# Linear_Power.net
KiCad netlist of a schematic drawn in Altium Designer
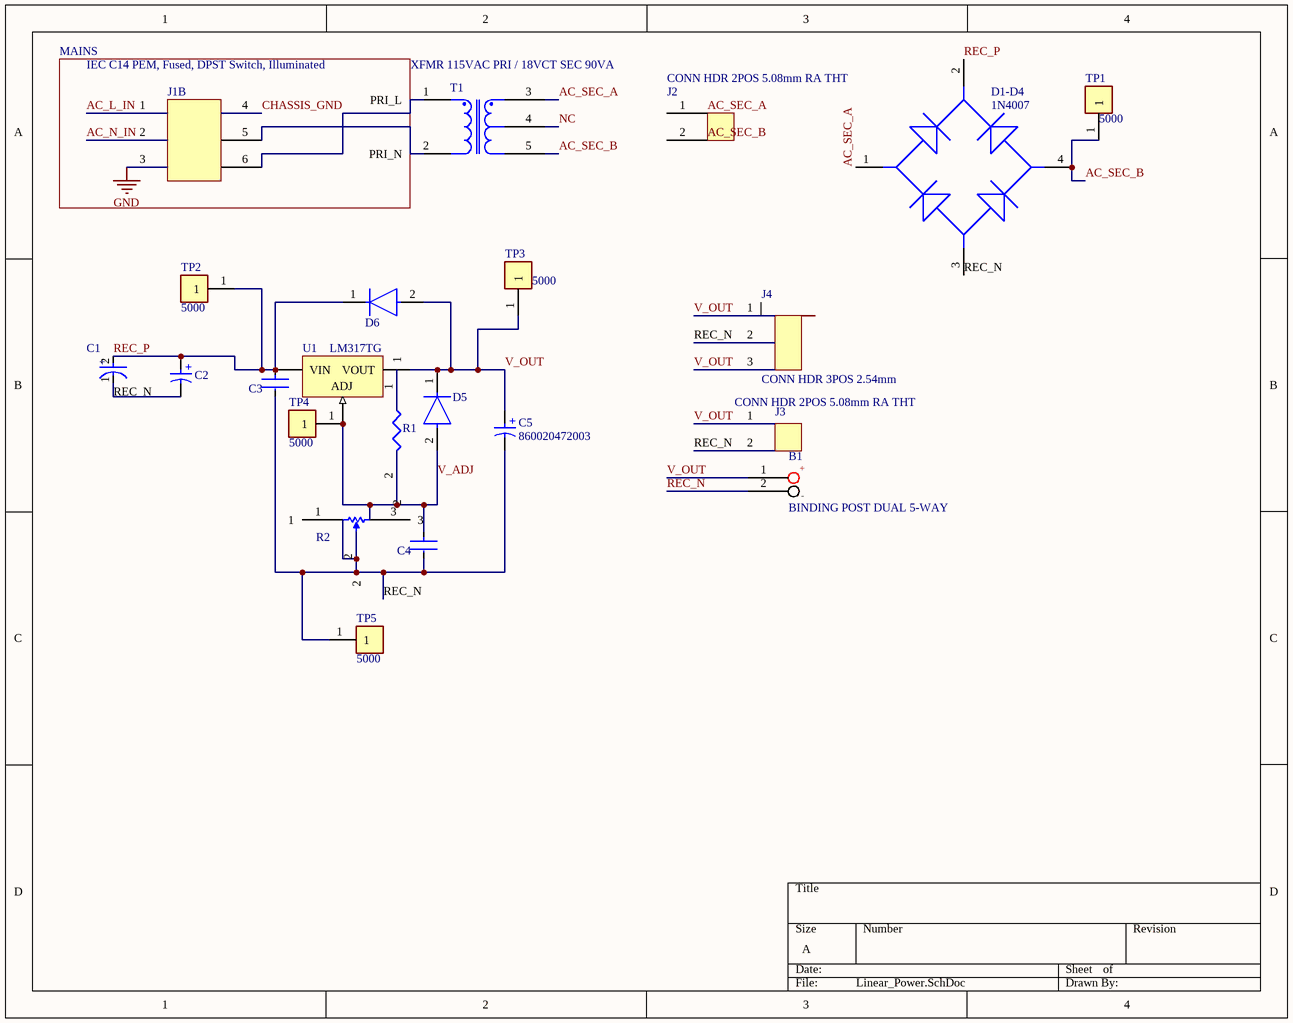
[diagram p0: Linear_Power.SchDoc]

(export (version "E")
  (design (tool "Eeschema 10.0.6"))
  (components
    (comp (ref "B1") (value "BINDING POST DUAL 5-WAY") (libsource (lib "Schlib1") (part "BU-P6883")))
    (comp (ref "C1")
      (value "UPW1V222MHD6")
      (footprint "FP-227AVG035MFBJ-MFG")
      (description "227AVG035MFBJ AVG Series 35 V 220 uF 8 x 12 mm LS=3.5 mm Radial Aluminum Polymer Capacitor")
      (fields (field (name "TOLERANCE") "20%"))
      (libsource (lib "Altium Content Vault") (part "a00bbbee19879c290e62620ae7e47b1"))
    )
    (comp (ref "C2")
      (value "UPJ1V101MPD")
      (footprint "WCAP-ATLI_D5H11")
      (description "WCAP-ATLI Aluminum Electrolytic Capacitors")
      (fields (field (name "TOLERANCE") "20%"))
      (libsource (lib "Altium Content Vault") (part "Capacitor_Polarized"))
    )
    (comp (ref "C3")
      (value "C410C104Z5U5TA7200")
      (footprint "FP-RHE0K1-MFG")
      (description "Multilayer Ceramic Capacitor, 0.1 uF, 50 V, -20%, +80%, Z5U, Axial Leaded")
      (libsource (lib "Altium Content Vault") (part "b4654b650e69147ec39a6b967a45e02"))
    )
    (comp (ref "C4")
      (value "C410C104Z5U5TA7200")
      (footprint "FP-RHE0K1-MFG")
      (description "Multilayer Ceramic Capacitor, 0.1 uF, 50 V, -20%, +80%, Z5U, Axial Leaded")
      (libsource (lib "Altium Content Vault") (part "b4654b650e69147ec39a6b967a45e02"))
    )
    (comp (ref "C5")
      (value "860020472003")
      (footprint "WCAP-ATG5_D5H11")
      (description "860020472003 WCAP-ATG5 Aluminum Electrolytic Capacitors")
      (fields (field (name "TOLERANCE") "20%"))
      (libsource (lib "Altium Content Vault") (part "Capacitor_Polarized"))
    )
    (comp (ref "D1-D4")
      (value "1N4007")
      (footprint "FP-KBJ-MFG")
      (description "BRIDGE RECT 1PHASE 800V 6A KBJ")
      (fields (field (name "MANUFACTURER") "Diodes") (field (name "MANUFACTURER PART NUMBER") "KBJ608G"))
      (libsource (lib "Altium Content Vault") (part "19e15813eaf9f16eb36100cfe986ca5"))
    )
    (comp (ref "D5")
      (value "1N4007")
      (footprint "FP-1N4007-MFG")
      (description "Rectifier diode 1000 V 1 A DO-41, ,")
      (fields
        (field (name "MANUFACTURER") "Diotec")
        (field (name "OCTOPART") "https://octopart.com/1n4007-diotec-4040411")
      )
      (libsource (lib "Altium Content Vault") (part "d7152d700b627762746794eb795d46e"))
    )
    (comp (ref "D6")
      (value "1N4007")
      (footprint "FP-1N4007-MFG")
      (description "Rectifier diode 1000 V 1 A DO-41, ,")
      (fields
        (field (name "MANUFACTURER") "Diotec")
        (field (name "OCTOPART") "https://octopart.com/1n4007-diotec-4040411")
      )
      (libsource (lib "Altium Content Vault") (part "d7152d700b627762746794eb795d46e"))
    )
    (comp (ref "J1")
      (value "IEC C14 PEM, Fused, DPST Switch, Illuminated")
      (description "Mains Power Connector")
      (fields
        (field (name "MANUFACTURER") "Qualtek")
        (field (name "MANUFACTURER PART NUMBER") "719W-UEL3BR51")
      )
      (libsource (lib "Schlib1") (part "719W-UEL3BR51"))
    )
    (comp (ref "J2")
      (value "CONN HDR 2POS 5.08mm RA THT")
      (footprint "OSTOQ025451")
      (description "2-position, 5.08mm pitch, shrouded, right-angle, through-hole header")
      (libsource (lib "Schlib1") (part "OSTOQ025451"))
    )
    (comp (ref "J3")
      (value "CONN HDR 2POS 5.08mm RA THT")
      (footprint "OSTOQ025451")
      (description "2-position, 5.08mm pitch, shrouded, right-angle, through-hole header")
      (libsource (lib "Schlib1") (part "OSTOQ025451"))
    )
    (comp (ref "J4")
      (value "CONN HDR 3POS 2.54mm")
      (footprint "Connector, header vertical 3-pos 2.54mm")
      (description "Header, 3-position, 0.1in pitch, straight, TH")
      (libsource (lib "Schlib1") (part "PRPC003SAAN-RC"))
    )
    (comp (ref "R1")
      (value "240 Ohm,1/4W,1%")
      (footprint "pp")
      (description "Through Hole Resistor 240 Ohm,1/4W,1%, Axial")
      (libsource (lib "Schlib1") (part "RNMF14FTC240R"))
    )
    (comp (ref "R2")
      (value "Potentiometer linear 4.7 kOhm±20 %,")
      (footprint "PC16SH07IP04-472A2020--TA")
      (description "Potentiometer linear 4.7 kOhm±20 %, PC16SH07IP04-472A2020--TA, Piher")
      (fields
        (field (name "MANUFACTURER") "Piher")
        (field (name "MANUFACTURER PART NUMBER") "PC16SH07IP04-472A2020--TA")
      )
      (libsource (lib "Schlib1") (part "PC16SH07IP04-472A2020--TA"))
    )
    (comp (ref "T1")
      (value "XFMR 115VAC PRI / 18VCT SEC 90VA")
      (fields (field (name "MANUFACTURER") "Hammond") (field (name "MANUFACTURER PART NUMBER") "166P18"))
      (libsource (lib "Schlib1") (part "166P18"))
    )
    (comp (ref "TP1")
      (value "5000")
      (footprint "FP-5000-MFG")
      (description "PC TEST POINT MINIATURE RED")
      (libsource (lib "") (part "1e4615820a309e3ce90f9e6d957b7fa_2"))
    )
    (comp (ref "TP2")
      (value "5000")
      (footprint "FP-5000-MFG")
      (description "PC TEST POINT MINIATURE RED")
      (libsource (lib "") (part "1e4615820a309e3ce90f9e6d957b7fa_1"))
    )
    (comp (ref "TP3")
      (value "5000")
      (footprint "FP-5000-MFG")
      (description "PC TEST POINT MINIATURE RED")
      (libsource (lib "") (part "1e4615820a309e3ce90f9e6d957b7fa_2"))
    )
    (comp (ref "TP4")
      (value "5000")
      (footprint "FP-5000-MFG")
      (description "PC TEST POINT MINIATURE RED")
      (libsource (lib "") (part "1e4615820a309e3ce90f9e6d957b7fa_1"))
    )
    (comp (ref "TP5")
      (value "5000")
      (footprint "FP-5000-MFG")
      (description "PC TEST POINT MINIATURE RED")
      (libsource (lib "Altium Content Vault") (part "1e4615820a309e3ce90f9e6d957b7fa"))
    )
    (comp (ref "U1")
      (value "LM317TG")
      (footprint "ONSC-TO-220-3-221AB-01")
      (libsource (lib "Altium Content Vault") (part "ONSC-LM317TG-3"))
    )
  )
  (nets
    (net (code "1") (name "/AC_L_IN") (class "Default")
      (node (ref "J1") (pin "1") (pinfunction "GND_IN_1") (pintype "passive"))
    )
    (net (code "2") (name "/AC_N_IN") (class "Default")
      (node (ref "J1") (pin "2") (pinfunction "N_IN_2") (pintype "passive"))
    )
    (net (code "3") (name "/AC_SEC_A") (class "Default")
      (node (ref "D1-D4") (pin "1") (pinfunction "+_1") (pintype "passive"))
      (node (ref "J2") (pin "1") (pinfunction "AC_SEC_1_1") (pintype "passive"))
    )
    (net (code "4") (name "/AC_SEC_B") (class "Default")
      (node (ref "D1-D4") (pin "4") (pinfunction "-_4") (pintype "passive"))
      (node (ref "J2") (pin "2") (pinfunction "AC_SEC_2_2") (pintype "passive"))
      (node (ref "TP1") (pin "1") (pinfunction "1_1") (pintype "passive"))
    )
    (net (code "5") (name "/CHASSIS_GND") (class "Default")
      (node (ref "J1") (pin "4") (pinfunction "GND_OUT_4") (pintype "passive"))
    )
    (net (code "7") (name "/REC_N") (class "Default")
      (node (ref "C1") (pin "1") (pinfunction "C_1") (pintype "passive"))
      (node (ref "C2") (pin "2") (pinfunction "N_2") (pintype "passive"))
      (node (ref "C3") (pin "2") (pinfunction "2_2") (pintype "passive"))
      (node (ref "C4") (pin "2") (pinfunction "2_2") (pintype "passive"))
      (node (ref "C5") (pin "2") (pinfunction "N_2") (pintype "passive"))
      (node (ref "D1-D4") (pin "3") (pinfunction "2_~_3") (pintype "passive"))
      (node (ref "J3") (pin "2") (pinfunction "AC_SEC_2_2") (pintype "passive"))
      (node (ref "J4") (pin "2") (pinfunction "2_2") (pintype "passive"))
      (node (ref "R2") (pin "1") (pinfunction "1_1") (pintype "passive"))
      (node (ref "R2") (pin "2") (pinfunction "2_2") (pintype "passive"))
      (node (ref "TP5") (pin "1") (pinfunction "1_1") (pintype "passive"))
    )
    (net (code "8") (name "/REC_P") (class "Default")
      (node (ref "C1") (pin "2") (pinfunction "A_2") (pintype "passive"))
      (node (ref "C2") (pin "1") (pinfunction "P_1") (pintype "passive"))
      (node (ref "C3") (pin "1") (pinfunction "1_1") (pintype "passive"))
      (node (ref "D1-D4") (pin "2") (pinfunction "1_~_2") (pintype "passive"))
      (node (ref "D6") (pin "1") (pinfunction "C_1") (pintype "passive"))
      (node (ref "TP2") (pin "1") (pinfunction "1_1") (pintype "passive"))
      (node (ref "U1") (pin "3") (pinfunction "VIN_3") (pintype "power_in"))
    )
    (net (code "9") (name "/V_ADJ") (class "Default")
      (node (ref "C4") (pin "1") (pinfunction "1_1") (pintype "passive"))
      (node (ref "D5") (pin "2") (pinfunction "A_2") (pintype "passive"))
      (node (ref "R1") (pin "2") (pinfunction "2_2") (pintype "passive"))
      (node (ref "R2") (pin "3") (pinfunction "3_3") (pintype "passive"))
      (node (ref "TP4") (pin "1") (pinfunction "1_1") (pintype "passive"))
      (node (ref "U1") (pin "1") (pinfunction "ADJ_1") (pintype "input"))
    )
    (net (code "10") (name "/V_OUT") (class "Default")
      (node (ref "C5") (pin "1") (pinfunction "P_1") (pintype "passive"))
      (node (ref "D5") (pin "1") (pinfunction "C_1") (pintype "passive"))
      (node (ref "D6") (pin "2") (pinfunction "A_2") (pintype "passive"))
      (node (ref "J3") (pin "1") (pinfunction "AC_SEC_1_1") (pintype "passive"))
      (node (ref "J4") (pin "1") (pinfunction "1_1") (pintype "passive"))
      (node (ref "J4") (pin "3") (pinfunction "3_3") (pintype "passive"))
      (node (ref "TP3") (pin "1") (pinfunction "1_1") (pintype "passive"))
      (node (ref "U1") (pin "2") (pinfunction "VOUT_2") (pintype "power_in"))
    )
    (net (code "11") (name "GND") (class "Default")
      (node (ref "J1") (pin "3") (pinfunction "L_IN_3") (pintype "passive"))
    )
    (net (code "12") (name "unconnected-(B1-V_OUT_NEG-Pad2)") (class "Default")
      (node (ref "B1") (pin "2") (pinfunction "V_OUT_NEG_2") (pintype "passive"))
    )
    (net (code "13") (name "unconnected-(B1-V_OUT_POS-Pad1)") (class "Default")
      (node (ref "B1") (pin "1") (pinfunction "V_OUT_POS_1") (pintype "passive"))
    )
    (net (code "14") (name "unconnected-(J1B-L_OUT-Pad6)") (class "Default")
      (node (ref "J1") (pin "6") (pinfunction "L_OUT_6") (pintype "passive"))
    )
    (net (code "15") (name "unconnected-(J1B-N_OUT-Pad5)") (class "Default")
      (node (ref "J1") (pin "5") (pinfunction "N_OUT_5") (pintype "passive"))
    )
    (net (code "16") (name "unconnected-(R1-Pad1)") (class "Default")
      (node (ref "R1") (pin "1") (pinfunction "1_1") (pintype "passive"))
    )
    (net (code "17") (name "unconnected-(T1-PRI_L-Pad1)") (class "Default")
      (node (ref "T1") (pin "1") (pinfunction "PRI_L_1") (pintype "passive"))
    )
    (net (code "18") (name "unconnected-(T1-PRI_N-Pad2)") (class "Default")
      (node (ref "T1") (pin "2") (pinfunction "PRI_N_2") (pintype "passive"))
    )
    (net (code "19") (name "unconnected-(T1-SEC_1-Pad3)") (class "Default")
      (node (ref "T1") (pin "3") (pinfunction "SEC_1_3") (pintype "passive"))
    )
    (net (code "20") (name "unconnected-(T1-SEC_2-Pad5)") (class "Default")
      (node (ref "T1") (pin "5") (pinfunction "SEC_2_5") (pintype "passive"))
    )
    (net (code "21") (name "unconnected-(T1-SEC_CT-Pad4)") (class "Default")
      (node (ref "T1") (pin "4") (pinfunction "SEC_CT_4") (pintype "passive"))
    )
  )
)
